# oscillator_classified.net
KiCad netlist of a schematic drawn in Altium Designer
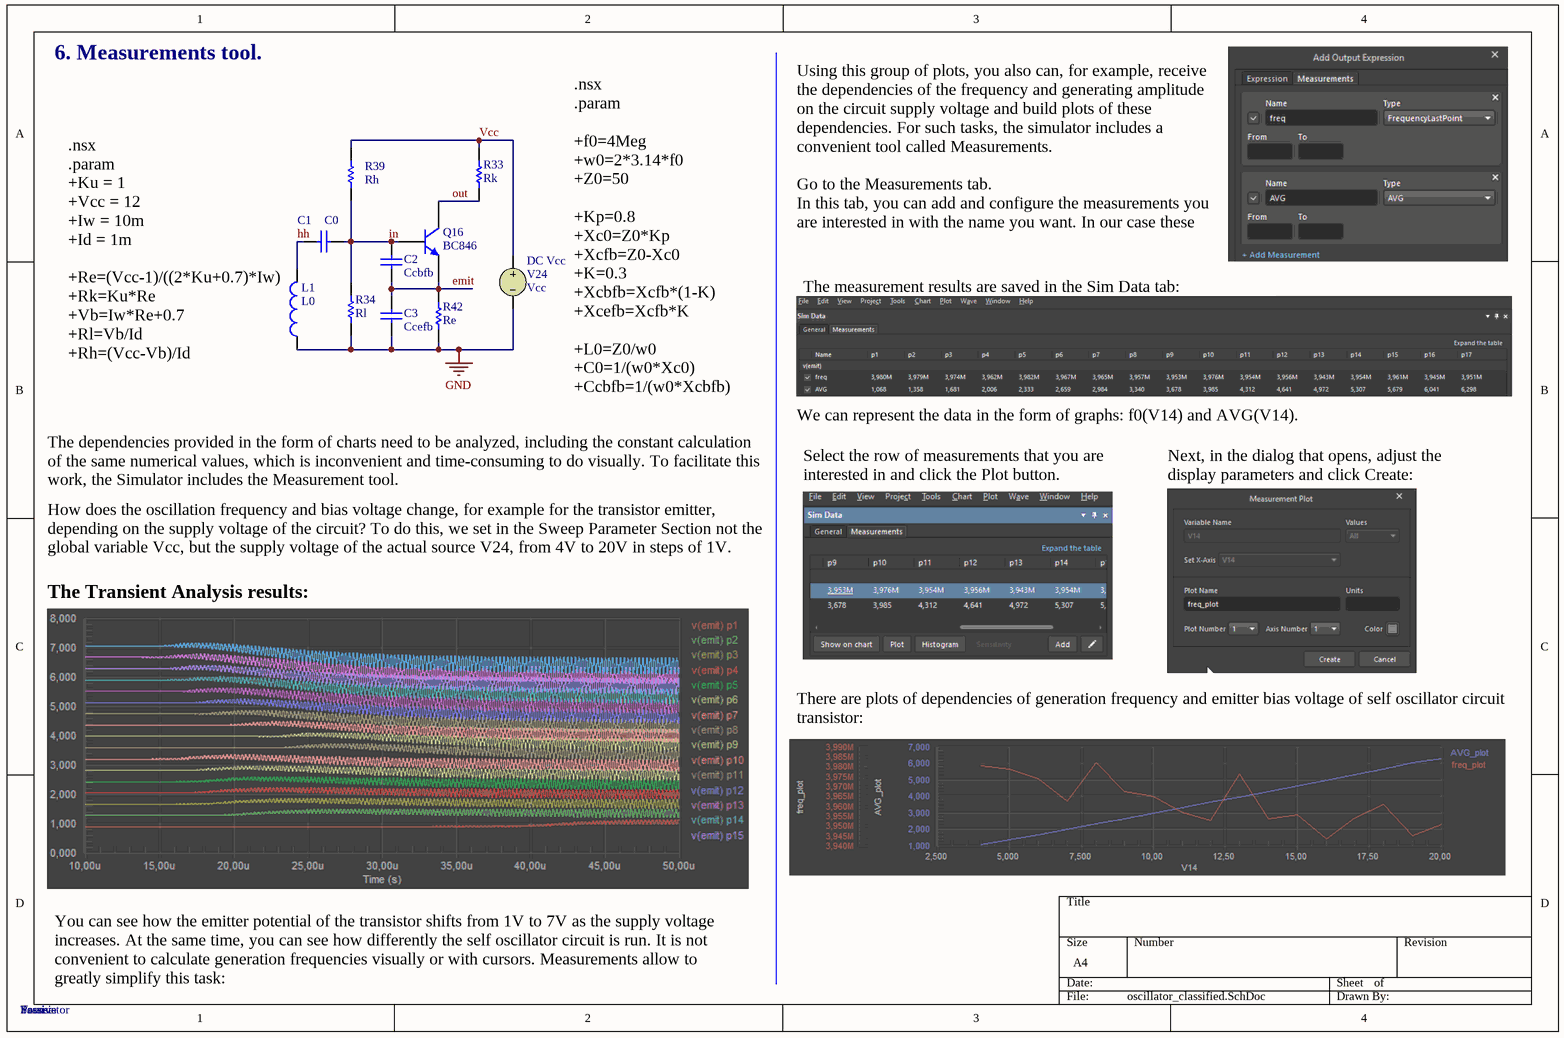
[diagram p0: oscillator_classified.SchDoc]

(export (version "E")
  (design (tool "Eeschema 10.0.6"))
  (components
    (comp (ref "C1")
      (value "C0")
      (description "Capacitor")
      (fields (field (name "CLASSIFICATION") "Passive"))
      (libsource (lib "Simulation Generic Components") (part "Capacitor"))
    )
    (comp (ref "C2")
      (value "Ccbfb")
      (description "Capacitor")
      (libsource (lib "Simulation Generic Components") (part "Capacitor"))
    )
    (comp (ref "C3")
      (value "Ccefb")
      (description "Capacitor")
      (fields (field (name "CLASSIFICATION") "Passive"))
      (libsource (lib "Simulation Generic Components") (part "Capacitor"))
    )
    (comp (ref "L1")
      (value "L0")
      (description "Inductor")
      (fields (field (name "CLASSIFICATION") "Passive"))
      (libsource (lib "Simulation Generic Components") (part "Inductor"))
    )
    (comp (ref "Q16")
      (value "BC846")
      (footprint "TO-92A")
      (description "NPN General Purpose Amplifier")
      (fields (field (name "CLASSIFICATION") "Transistor") (field (name "PUBLISHER") "Altium Limited"))
      (libsource (lib "Miscellaneous Devices") (part "2N3904"))
    )
    (comp (ref "R33")
      (value "Rk")
      (description "Resistor")
      (fields (field (name "CLASSIFICATION") "Passive"))
      (libsource (lib "Simulation Generic Components") (part "Resistor"))
    )
    (comp (ref "R34")
      (value "Rl")
      (description "Resistor")
      (fields (field (name "CLASSIFICATION") "Passive"))
      (libsource (lib "Simulation Generic Components") (part "Resistor"))
    )
    (comp (ref "R39")
      (value "Rh")
      (description "Resistor")
      (fields (field (name "CLASSIFICATION") "Passive"))
      (libsource (lib "Simulation Generic Components") (part "Resistor"))
    )
    (comp (ref "R42")
      (value "Re")
      (description "Resistor")
      (fields (field (name "CLASSIFICATION") "Passive"))
      (libsource (lib "Simulation Generic Components") (part "Resistor"))
    )
    (comp (ref "V24")
      (value "DC Vcc")
      (description "Voltage Source")
      (fields
        (field (name "ALTIUM_VALUE") "Vcc")
        (field (name "CLASSIFICATION") "Source")
        (field (name "PUBLISHER") "Altium Limited")
      )
      (libsource (lib "Simulation Generic Components") (part "VSRC"))
    )
  )
  (nets
    (net (code "1") (name "/Vcc") (class "Default")
      (node (ref "R33") (pin "2") (pinfunction "2_2") (pintype "passive"))
      (node (ref "R39") (pin "2") (pinfunction "2_2") (pintype "passive"))
      (node (ref "V24") (pin "1") (pinfunction "1_1") (pintype "passive"))
    )
    (net (code "2") (name "/emit") (class "Default")
      (node (ref "C2") (pin "1") (pinfunction "1_1") (pintype "passive"))
      (node (ref "C3") (pin "2") (pinfunction "2_2") (pintype "passive"))
      (node (ref "Q16") (pin "1") (pinfunction "E_1") (pintype "passive"))
      (node (ref "R42") (pin "2") (pinfunction "2_2") (pintype "passive"))
    )
    (net (code "3") (name "/hh") (class "Default")
      (node (ref "C1") (pin "1") (pinfunction "1_1") (pintype "passive"))
      (node (ref "L1") (pin "2") (pinfunction "2_2") (pintype "passive"))
    )
    (net (code "4") (name "/in") (class "Default")
      (node (ref "C1") (pin "2") (pinfunction "2_2") (pintype "passive"))
      (node (ref "C2") (pin "2") (pinfunction "2_2") (pintype "passive"))
      (node (ref "Q16") (pin "2") (pinfunction "B_2") (pintype "passive"))
      (node (ref "R34") (pin "1") (pinfunction "1_1") (pintype "passive"))
      (node (ref "R39") (pin "1") (pinfunction "1_1") (pintype "passive"))
    )
    (net (code "5") (name "/out") (class "Default")
      (node (ref "Q16") (pin "3") (pinfunction "C_3") (pintype "passive"))
      (node (ref "R33") (pin "1") (pinfunction "1_1") (pintype "passive"))
    )
    (net (code "6") (name "GND") (class "Default")
      (node (ref "C3") (pin "1") (pinfunction "1_1") (pintype "passive"))
      (node (ref "L1") (pin "1") (pinfunction "1_1") (pintype "passive"))
      (node (ref "R34") (pin "2") (pinfunction "2_2") (pintype "passive"))
      (node (ref "R42") (pin "1") (pinfunction "1_1") (pintype "passive"))
      (node (ref "V24") (pin "2") (pinfunction "2_2") (pintype "passive"))
    )
  )
)
